# 04_Power_Supply.net
KiCad netlist of a schematic drawn in Altium Designer
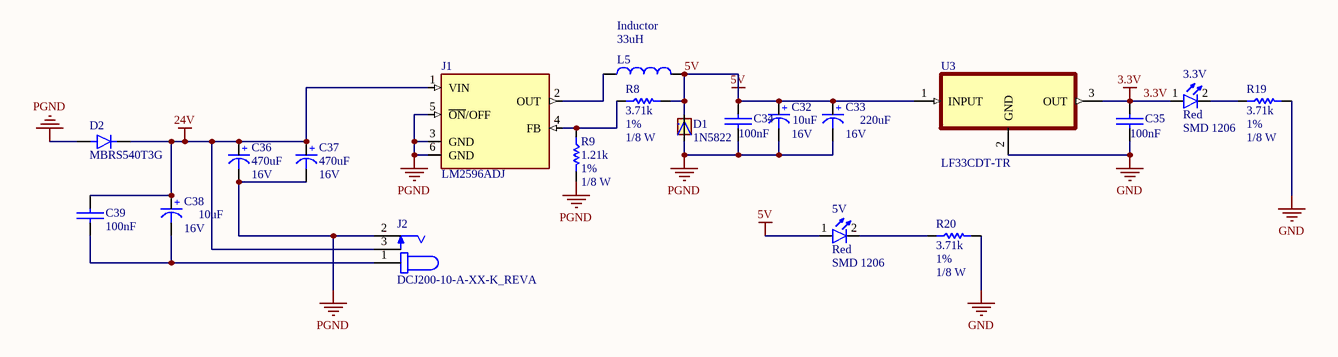
[diagram p0: 04_Power_Supply.SchDoc]

(export (version "E")
  (design (tool "Eeschema 10.0.6"))
  (components
    (comp (ref "3.3V")
      (value "Red")
      (footprint "LED SMD 1206")
      (description "LED")
      (fields
        (field (name "COLOR") "Red")
        (field (name "SIZE") "SMD 1206")
        (field (name "DESIGNER") "Saeid Jorablo")
      )
      (libsource (lib "My Library") (part "LED"))
    )
    (comp (ref "5V")
      (value "Red")
      (footprint "LED SMD 1206")
      (description "LED")
      (fields
        (field (name "COLOR") "Red")
        (field (name "SIZE") "SMD 1206")
        (field (name "DESIGNER") "Saeid Jorablo")
      )
      (libsource (lib "My Library") (part "LED"))
    )
    (comp (ref "C32")
      (value "10uF")
      (footprint "cap 01")
      (description "Polar Capacitor")
      (fields (field (name "VOLTAGE") "16V") (field (name "DESIGNER") "Saeid Jorablo"))
      (libsource (lib "My Library") (part "Cap-Polar"))
    )
    (comp (ref "C33")
      (value "220uF")
      (footprint "cap 01")
      (description "Polar Capacitor")
      (fields (field (name "VOLTAGE") "16V") (field (name "DESIGNER") "Saeid Jorablo"))
      (libsource (lib "My Library") (part "Cap-Polar"))
    )
    (comp (ref "C34")
      (value "100nF")
      (footprint "SMD_CAP_1206")
      (description "Bipolar Capacitor")
      (fields (field (name "VOLTAGE") "100V") (field (name "DESIGNER") "Saeid Jorablo"))
      (libsource (lib "My Library") (part "Cap-Bipolar"))
    )
    (comp (ref "C35")
      (value "100nF")
      (footprint "SMD_CAP_1206")
      (description "Bipolar Capacitor")
      (fields (field (name "VOLTAGE") "100V") (field (name "DESIGNER") "Saeid Jorablo"))
      (libsource (lib "My Library") (part "Cap-Bipolar"))
    )
    (comp (ref "C36")
      (value "470uF")
      (footprint "cap 01")
      (description "Polar Capacitor")
      (fields (field (name "VOLTAGE") "16V") (field (name "DESIGNER") "Saeid Jorablo"))
      (libsource (lib "My Library") (part "Cap-Polar"))
    )
    (comp (ref "C37")
      (value "470uF")
      (footprint "cap 01")
      (description "Polar Capacitor")
      (fields (field (name "VOLTAGE") "16V") (field (name "DESIGNER") "Saeid Jorablo"))
      (libsource (lib "My Library") (part "Cap-Polar"))
    )
    (comp (ref "C38")
      (value "10uF")
      (footprint "cap 01")
      (description "Polar Capacitor")
      (fields (field (name "VOLTAGE") "16V") (field (name "DESIGNER") "Saeid Jorablo"))
      (libsource (lib "My Library") (part "Cap-Polar"))
    )
    (comp (ref "C39")
      (value "100nF")
      (footprint "SMD_CAP_1206")
      (description "Bipolar Capacitor")
      (fields (field (name "VOLTAGE") "100V") (field (name "DESIGNER") "Saeid Jorablo"))
      (libsource (lib "My Library") (part "Cap-Bipolar"))
    )
    (comp (ref "D1")
      (value "1N5822")
      (footprint "DIOAD2120W130L950D530P")
      (description "Schottky, DO-201, 40V, 3A, 150Â°C")
      (fields (field (name "MF") "Diotec Semiconductor"))
      (libsource (lib "1N5822") (part "1N5822"))
    )
    (comp (ref "D2")
      (value "MBRS540T3G")
      (footprint "DIOM7959X261N")
      (description "Diode Schottky 40 V 5A Surface Mount SMC")
      (fields (field (name "MF") "ON Semiconductor"))
      (libsource (lib "MBRS540T3G") (part "MBRS540T3G"))
    )
    (comp (ref "J1")
      (value "LM2596ADJ")
      (footprint "LM2596ADJ")
      (description "Convertidor de potencia SIMPLE SWITCHER")
      (fields (field (name "MF") "Texas Instruments") (field (name "MP") "LM2596-ADJ"))
      (libsource (lib "LM2596ADJ") (part "LM2596ADJ"))
    )
    (comp (ref "J2")
      (value "DCJ200-10-A-XX-K_REVA")
      (footprint "GCT_DCJ200-10-A-XX-K_REVA")
      (description "Power Barrel Connector Jack 2.05mm ID (0.081), 5.50mm OD (0.217) Through Hole, Right Angle")
      (fields (field (name "MF") "Global Connector Technology") (field (name "MP") "DCJ200-10-A-K1-K"))
      (libsource (lib "DCJ200-10-A-XX-K_REVA") (part "DCJ200-10-A-XX-K_REVA"))
    )
    (comp (ref "L5")
      (value "Inductor")
      (footprint "INDC1608L")
      (fields (field (name "ALTIUM_VALUE") "33uH") (field (name "PUBLISHER") "Altium Limited"))
      (libsource (lib "My Library") (part "Inductor"))
    )
    (comp (ref "R8")
      (value "3.71k")
      (footprint "RES 0805 (2012X06L)")
      (description "Resistor")
      (fields (field (name "TOLERANCE") "1%") (field (name "POWER") "1/8 W"))
      (libsource (lib "My Library") (part "Resistor"))
    )
    (comp (ref "R9")
      (value "1.21k")
      (footprint "RES 0805 (2012X06L)")
      (description "Resistor")
      (fields (field (name "TOLERANCE") "1%") (field (name "POWER") "1/8 W"))
      (libsource (lib "My Library") (part "Resistor"))
    )
    (comp (ref "R19")
      (value "3.71k")
      (footprint "RES 0805 (2012X06L)")
      (description "Resistor")
      (fields (field (name "TOLERANCE") "1%") (field (name "POWER") "1/8 W"))
      (libsource (lib "My Library") (part "Resistor"))
    )
    (comp (ref "R20")
      (value "3.71k")
      (footprint "RES 0805 (2012X06L)")
      (description "Resistor")
      (fields (field (name "TOLERANCE") "1%") (field (name "POWER") "1/8 W"))
      (libsource (lib "My Library") (part "Resistor"))
    )
    (comp (ref "U3")
      (value "LF33CDT-TR")
      (footprint "TO228P972X240-3N")
      (description "Linear Voltage Regulator IC Positive Fixed 1 Output 500mA DPAK")
      (fields (field (name "MF") "STMicroelectronics"))
      (libsource (lib "LF33CDT-TR") (part "LF33CDT-TR"))
    )
  )
  (nets
    (net (code "1") (name "3.3V") (class "Default")
      (node (ref "3.3V") (pin "1") (pinfunction "A_1") (pintype "passive"))
      (node (ref "C35") (pin "2") (pinfunction "-_2") (pintype "passive"))
      (node (ref "U3") (pin "3") (pinfunction "OUT_3") (pintype "output"))
    )
    (net (code "2") (name "5V") (class "Default")
      (node (ref "5V") (pin "1") (pinfunction "A_1") (pintype "passive"))
      (node (ref "C32") (pin "1") (pinfunction "+_1") (pintype "passive"))
      (node (ref "C33") (pin "1") (pinfunction "+_1") (pintype "passive"))
      (node (ref "C34") (pin "2") (pinfunction "-_2") (pintype "passive"))
      (node (ref "D1") (pin "C") (pinfunction "C_C") (pintype "passive"))
      (node (ref "L5") (pin "2") (pinfunction "2_2") (pintype "passive"))
      (node (ref "R8") (pin "2") (pinfunction "2_2") (pintype "passive"))
      (node (ref "U3") (pin "1") (pinfunction "INPUT_1") (pintype "input"))
    )
    (net (code "3") (name "24V") (class "Default")
      (node (ref "C36") (pin "1") (pinfunction "+_1") (pintype "passive"))
      (node (ref "C37") (pin "1") (pinfunction "+_1") (pintype "passive"))
      (node (ref "C38") (pin "1") (pinfunction "+_1") (pintype "passive"))
      (node (ref "C39") (pin "2") (pinfunction "-_2") (pintype "passive"))
      (node (ref "D2") (pin "1") (pinfunction "C_1") (pintype "passive"))
      (node (ref "J1") (pin "1") (pinfunction "VIN_1") (pintype "input"))
      (node (ref "J2") (pin "3") (pinfunction "3_3") (pintype "passive"))
    )
    (net (code "4") (name "GND") (class "Default")
      (node (ref "C35") (pin "1") (pinfunction "+_1") (pintype "passive"))
      (node (ref "R19") (pin "2") (pinfunction "2_2") (pintype "passive"))
      (node (ref "R20") (pin "2") (pinfunction "2_2") (pintype "passive"))
      (node (ref "U3") (pin "2") (pinfunction "GND_2") (pintype "passive"))
    )
    (net (code "5") (name "Net-(3.3V-K)") (class "Default")
      (node (ref "3.3V") (pin "2") (pinfunction "K_2") (pintype "passive"))
      (node (ref "R19") (pin "1") (pinfunction "1_1") (pintype "passive"))
    )
    (net (code "6") (name "Net-(5V-K)") (class "Default")
      (node (ref "5V") (pin "2") (pinfunction "K_2") (pintype "passive"))
      (node (ref "R20") (pin "1") (pinfunction "1_1") (pintype "passive"))
    )
    (net (code "7") (name "Net-(C38--)") (class "Default")
      (node (ref "C38") (pin "2") (pinfunction "-_2") (pintype "passive"))
      (node (ref "C39") (pin "1") (pinfunction "+_1") (pintype "passive"))
      (node (ref "J2") (pin "1") (pinfunction "1_1") (pintype "passive"))
    )
    (net (code "8") (name "Net-(J1-FB)") (class "Default")
      (node (ref "J1") (pin "4") (pinfunction "FB_4") (pintype "input"))
      (node (ref "R8") (pin "1") (pinfunction "1_1") (pintype "passive"))
      (node (ref "R9") (pin "1") (pinfunction "1_1") (pintype "passive"))
    )
    (net (code "9") (name "Net-(J1-OUT)") (class "Default")
      (node (ref "J1") (pin "2") (pinfunction "OUT_2") (pintype "output"))
      (node (ref "L5") (pin "1") (pinfunction "1_1") (pintype "passive"))
    )
    (net (code "10") (name "PGND") (class "Default")
      (node (ref "C32") (pin "2") (pinfunction "-_2") (pintype "passive"))
      (node (ref "C33") (pin "2") (pinfunction "-_2") (pintype "passive"))
      (node (ref "C34") (pin "1") (pinfunction "+_1") (pintype "passive"))
      (node (ref "C36") (pin "2") (pinfunction "-_2") (pintype "passive"))
      (node (ref "C37") (pin "2") (pinfunction "-_2") (pintype "passive"))
      (node (ref "D1") (pin "A") (pinfunction "A_A") (pintype "passive"))
      (node (ref "D2") (pin "2") (pinfunction "A_2") (pintype "passive"))
      (node (ref "J1") (pin "3") (pinfunction "GND_3") (pintype "power_in"))
      (node (ref "J1") (pin "5") (pinfunction "~{ON}/OFF_5") (pintype "input"))
      (node (ref "J1") (pin "6") (pinfunction "GND_6") (pintype "power_in"))
      (node (ref "J2") (pin "2") (pinfunction "2_2") (pintype "passive"))
      (node (ref "R9") (pin "2") (pinfunction "2_2") (pintype "passive"))
    )
  )
)
